# outgoing_connection.net
KiCad netlist of a schematic drawn in Altium Designer
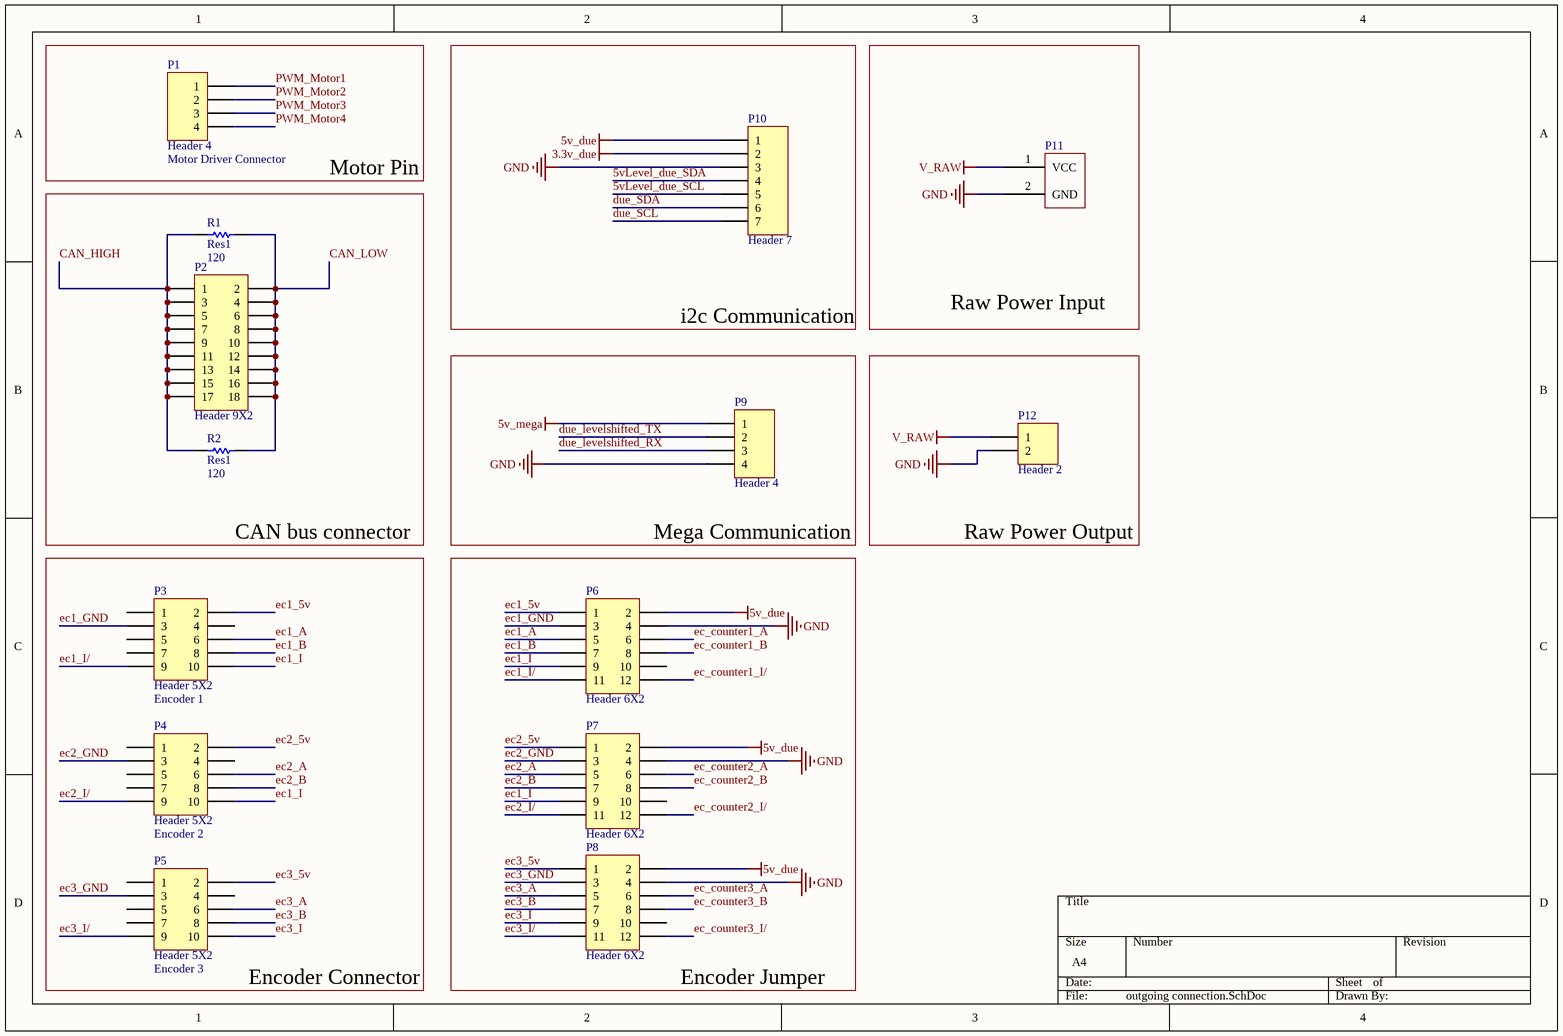
[diagram p0: outgoing connection.SchDoc]

(export (version "E")
  (design (tool "Eeschema 10.0.6"))
  (components
    (comp (ref "P1")
      (value "Header 4")
      (footprint "HDR1X4")
      (description "Header, 4-Pin")
      (fields (field (name "USAGE") "Motor Driver Connector") (field (name "PUBLISHER") "Altium Limited"))
      (libsource (lib "") (part "Header 4_1"))
    )
    (comp (ref "P2")
      (value "Header 9X2")
      (footprint "HDR2X9")
      (description "Header, 9-Pin, Dual row")
      (fields (field (name "PUBLISHER") "Altium Limited"))
      (libsource (lib "Miscellaneous Connectors") (part "Header 9X2"))
    )
    (comp (ref "P3")
      (value "Header 5X2")
      (footprint "HDR2X5")
      (description "Header, 5-Pin, Dual row")
      (fields (field (name "USAGE") "Encoder 1") (field (name "PUBLISHER") "Altium Limited"))
      (libsource (lib "Miscellaneous Connectors") (part "Header 5X2"))
    )
    (comp (ref "P4")
      (value "Header 5X2")
      (footprint "HDR2X5")
      (description "Header, 5-Pin, Dual row")
      (fields (field (name "USAGE") "Encoder 2") (field (name "PUBLISHER") "Altium Limited"))
      (libsource (lib "Miscellaneous Connectors") (part "Header 5X2"))
    )
    (comp (ref "P5")
      (value "Header 5X2")
      (footprint "HDR2X5")
      (description "Header, 5-Pin, Dual row")
      (fields (field (name "USAGE") "Encoder 3") (field (name "PUBLISHER") "Altium Limited"))
      (libsource (lib "Miscellaneous Connectors") (part "Header 5X2"))
    )
    (comp (ref "P6")
      (value "Header 6X2")
      (footprint "HDR2X6")
      (description "Header, 6-Pin, Dual row")
      (fields (field (name "PUBLISHER") "Altium Limited"))
      (libsource (lib "Miscellaneous Connectors") (part "Header 6X2"))
    )
    (comp (ref "P7")
      (value "Header 6X2")
      (footprint "HDR2X6")
      (description "Header, 6-Pin, Dual row")
      (fields (field (name "PUBLISHER") "Altium Limited"))
      (libsource (lib "Miscellaneous Connectors") (part "Header 6X2"))
    )
    (comp (ref "P8")
      (value "Header 6X2")
      (footprint "HDR2X6")
      (description "Header, 6-Pin, Dual row")
      (fields (field (name "PUBLISHER") "Altium Limited"))
      (libsource (lib "Miscellaneous Connectors") (part "Header 6X2"))
    )
    (comp (ref "P9")
      (value "Header 4")
      (footprint "HDR1X4")
      (description "Header, 4-Pin")
      (fields (field (name "PUBLISHER") "Altium Limited"))
      (libsource (lib "Miscellaneous Connectors") (part "Header 4"))
    )
    (comp (ref "P10")
      (value "Header 7")
      (footprint "HDR1X7")
      (description "Header, 7-Pin")
      (fields (field (name "PUBLISHER") "Altium Limited"))
      (libsource (lib "Miscellaneous Connectors") (part "Header 7"))
    )
    (comp (ref "P11")
      (value "big Pin power port")
      (footprint "bigPin_power_port")
      (libsource (lib "bigPin_power_port") (part "big Pin power port"))
    )
    (comp (ref "P12")
      (value "Header 2")
      (footprint "HDR1X2")
      (description "Header, 2-Pin")
      (fields (field (name "PUBLISHER") "Altium Limited"))
      (libsource (lib "Miscellaneous Connectors") (part "Header 2"))
    )
    (comp (ref "R1")
      (value "Res1")
      (footprint "AXIAL-0.3")
      (description "Resistor")
      (fields (field (name "ALTIUM_VALUE") "120") (field (name "PUBLISHER") "Altium Limited"))
      (libsource (lib "Miscellaneous Devices") (part "Res1"))
    )
    (comp (ref "R2")
      (value "Res1")
      (footprint "AXIAL-0.3")
      (description "Resistor")
      (fields (field (name "ALTIUM_VALUE") "120") (field (name "PUBLISHER") "Altium Limited"))
      (libsource (lib "Miscellaneous Devices") (part "Res1"))
    )
  )
  (nets
    (net (code "1") (name "/5vLevel_due_SCL") (class "Default")
      (node (ref "P10") (pin "5") (pinfunction "5_5") (pintype "passive"))
    )
    (net (code "2") (name "/5vLevel_due_SDA") (class "Default")
      (node (ref "P10") (pin "4") (pinfunction "4_4") (pintype "passive"))
    )
    (net (code "3") (name "/CAN_HIGH") (class "Default")
      (node (ref "P2") (pin "1") (pinfunction "1_1") (pintype "passive"))
      (node (ref "P2") (pin "11") (pinfunction "11_11") (pintype "passive"))
      (node (ref "P2") (pin "13") (pinfunction "13_13") (pintype "passive"))
      (node (ref "P2") (pin "15") (pinfunction "15_15") (pintype "passive"))
      (node (ref "P2") (pin "17") (pinfunction "17_17") (pintype "passive"))
      (node (ref "P2") (pin "3") (pinfunction "3_3") (pintype "passive"))
      (node (ref "P2") (pin "5") (pinfunction "5_5") (pintype "passive"))
      (node (ref "P2") (pin "7") (pinfunction "7_7") (pintype "passive"))
      (node (ref "P2") (pin "9") (pinfunction "9_9") (pintype "passive"))
      (node (ref "R1") (pin "1") (pinfunction "1_1") (pintype "passive"))
      (node (ref "R2") (pin "1") (pinfunction "1_1") (pintype "passive"))
    )
    (net (code "4") (name "/CAN_LOW") (class "Default")
      (node (ref "P2") (pin "10") (pinfunction "10_10") (pintype "passive"))
      (node (ref "P2") (pin "12") (pinfunction "12_12") (pintype "passive"))
      (node (ref "P2") (pin "14") (pinfunction "14_14") (pintype "passive"))
      (node (ref "P2") (pin "16") (pinfunction "16_16") (pintype "passive"))
      (node (ref "P2") (pin "18") (pinfunction "18_18") (pintype "passive"))
      (node (ref "P2") (pin "2") (pinfunction "2_2") (pintype "passive"))
      (node (ref "P2") (pin "4") (pinfunction "4_4") (pintype "passive"))
      (node (ref "P2") (pin "6") (pinfunction "6_6") (pintype "passive"))
      (node (ref "P2") (pin "8") (pinfunction "8_8") (pintype "passive"))
      (node (ref "R1") (pin "2") (pinfunction "2_2") (pintype "passive"))
      (node (ref "R2") (pin "2") (pinfunction "2_2") (pintype "passive"))
    )
    (net (code "5") (name "/PWM_Motor1") (class "Default")
      (node (ref "P1") (pin "1") (pinfunction "1_1") (pintype "passive"))
    )
    (net (code "6") (name "/PWM_Motor2") (class "Default")
      (node (ref "P1") (pin "2") (pinfunction "2_2") (pintype "passive"))
    )
    (net (code "7") (name "/PWM_Motor3") (class "Default")
      (node (ref "P1") (pin "3") (pinfunction "3_3") (pintype "passive"))
    )
    (net (code "8") (name "/PWM_Motor4") (class "Default")
      (node (ref "P1") (pin "4") (pinfunction "4_4") (pintype "passive"))
    )
    (net (code "9") (name "/due_SCL") (class "Default")
      (node (ref "P10") (pin "7") (pinfunction "7_7") (pintype "passive"))
    )
    (net (code "10") (name "/due_SDA") (class "Default")
      (node (ref "P10") (pin "6") (pinfunction "6_6") (pintype "passive"))
    )
    (net (code "11") (name "/due_levelshifted_RX") (class "Default")
      (node (ref "P9") (pin "3") (pinfunction "3_3") (pintype "passive"))
    )
    (net (code "12") (name "/due_levelshifted_TX") (class "Default")
      (node (ref "P9") (pin "2") (pinfunction "2_2") (pintype "passive"))
    )
    (net (code "13") (name "/ec1_5v") (class "Default")
      (node (ref "P3") (pin "2") (pinfunction "2_2") (pintype "passive"))
      (node (ref "P6") (pin "1") (pinfunction "1_1") (pintype "passive"))
    )
    (net (code "14") (name "/ec1_A") (class "Default")
      (node (ref "P3") (pin "6") (pinfunction "6_6") (pintype "passive"))
      (node (ref "P6") (pin "5") (pinfunction "5_5") (pintype "passive"))
    )
    (net (code "15") (name "/ec1_B") (class "Default")
      (node (ref "P3") (pin "8") (pinfunction "8_8") (pintype "passive"))
      (node (ref "P6") (pin "7") (pinfunction "7_7") (pintype "passive"))
    )
    (net (code "16") (name "/ec1_GND") (class "Default")
      (node (ref "P3") (pin "3") (pinfunction "3_3") (pintype "passive"))
      (node (ref "P6") (pin "3") (pinfunction "3_3") (pintype "passive"))
    )
    (net (code "17") (name "/ec1_I") (class "Default")
      (node (ref "P3") (pin "10") (pinfunction "10_10") (pintype "passive"))
      (node (ref "P4") (pin "10") (pinfunction "10_10") (pintype "passive"))
      (node (ref "P6") (pin "9") (pinfunction "9_9") (pintype "passive"))
      (node (ref "P7") (pin "9") (pinfunction "9_9") (pintype "passive"))
    )
    (net (code "18") (name "/ec1_I{slash}") (class "Default")
      (node (ref "P3") (pin "9") (pinfunction "9_9") (pintype "passive"))
      (node (ref "P6") (pin "11") (pinfunction "11_11") (pintype "passive"))
    )
    (net (code "19") (name "/ec2_5v") (class "Default")
      (node (ref "P4") (pin "2") (pinfunction "2_2") (pintype "passive"))
      (node (ref "P7") (pin "1") (pinfunction "1_1") (pintype "passive"))
    )
    (net (code "20") (name "/ec2_A") (class "Default")
      (node (ref "P4") (pin "6") (pinfunction "6_6") (pintype "passive"))
      (node (ref "P7") (pin "5") (pinfunction "5_5") (pintype "passive"))
    )
    (net (code "21") (name "/ec2_B") (class "Default")
      (node (ref "P4") (pin "8") (pinfunction "8_8") (pintype "passive"))
      (node (ref "P7") (pin "7") (pinfunction "7_7") (pintype "passive"))
    )
    (net (code "22") (name "/ec2_GND") (class "Default")
      (node (ref "P4") (pin "3") (pinfunction "3_3") (pintype "passive"))
      (node (ref "P7") (pin "3") (pinfunction "3_3") (pintype "passive"))
    )
    (net (code "23") (name "/ec2_I{slash}") (class "Default")
      (node (ref "P4") (pin "9") (pinfunction "9_9") (pintype "passive"))
      (node (ref "P7") (pin "11") (pinfunction "11_11") (pintype "passive"))
    )
    (net (code "24") (name "/ec3_5v") (class "Default")
      (node (ref "P5") (pin "2") (pinfunction "2_2") (pintype "passive"))
      (node (ref "P8") (pin "1") (pinfunction "1_1") (pintype "passive"))
    )
    (net (code "25") (name "/ec3_A") (class "Default")
      (node (ref "P5") (pin "6") (pinfunction "6_6") (pintype "passive"))
      (node (ref "P8") (pin "5") (pinfunction "5_5") (pintype "passive"))
    )
    (net (code "26") (name "/ec3_B") (class "Default")
      (node (ref "P5") (pin "8") (pinfunction "8_8") (pintype "passive"))
      (node (ref "P8") (pin "7") (pinfunction "7_7") (pintype "passive"))
    )
    (net (code "27") (name "/ec3_GND") (class "Default")
      (node (ref "P5") (pin "3") (pinfunction "3_3") (pintype "passive"))
      (node (ref "P8") (pin "3") (pinfunction "3_3") (pintype "passive"))
    )
    (net (code "28") (name "/ec3_I") (class "Default")
      (node (ref "P5") (pin "10") (pinfunction "10_10") (pintype "passive"))
      (node (ref "P8") (pin "9") (pinfunction "9_9") (pintype "passive"))
    )
    (net (code "29") (name "/ec3_I{slash}") (class "Default")
      (node (ref "P5") (pin "9") (pinfunction "9_9") (pintype "passive"))
      (node (ref "P8") (pin "11") (pinfunction "11_11") (pintype "passive"))
    )
    (net (code "30") (name "/ec_counter1_A") (class "Default")
      (node (ref "P6") (pin "6") (pinfunction "6_6") (pintype "passive"))
    )
    (net (code "31") (name "/ec_counter1_B") (class "Default")
      (node (ref "P6") (pin "8") (pinfunction "8_8") (pintype "passive"))
    )
    (net (code "32") (name "/ec_counter1_I{slash}") (class "Default")
      (node (ref "P6") (pin "12") (pinfunction "12_12") (pintype "passive"))
    )
    (net (code "33") (name "/ec_counter2_A") (class "Default")
      (node (ref "P7") (pin "6") (pinfunction "6_6") (pintype "passive"))
    )
    (net (code "34") (name "/ec_counter2_B") (class "Default")
      (node (ref "P7") (pin "8") (pinfunction "8_8") (pintype "passive"))
    )
    (net (code "35") (name "/ec_counter2_I{slash}") (class "Default")
      (node (ref "P7") (pin "12") (pinfunction "12_12") (pintype "passive"))
    )
    (net (code "36") (name "/ec_counter3_A") (class "Default")
      (node (ref "P8") (pin "6") (pinfunction "6_6") (pintype "passive"))
    )
    (net (code "37") (name "/ec_counter3_B") (class "Default")
      (node (ref "P8") (pin "8") (pinfunction "8_8") (pintype "passive"))
    )
    (net (code "38") (name "/ec_counter3_I{slash}") (class "Default")
      (node (ref "P8") (pin "12") (pinfunction "12_12") (pintype "passive"))
    )
    (net (code "39") (name "3.3v_due") (class "Default")
      (node (ref "P10") (pin "2") (pinfunction "2_2") (pintype "passive"))
    )
    (net (code "40") (name "5v_due") (class "Default")
      (node (ref "P10") (pin "1") (pinfunction "1_1") (pintype "passive"))
      (node (ref "P6") (pin "2") (pinfunction "2_2") (pintype "passive"))
      (node (ref "P7") (pin "2") (pinfunction "2_2") (pintype "passive"))
      (node (ref "P8") (pin "2") (pinfunction "2_2") (pintype "passive"))
    )
    (net (code "41") (name "5v_mega") (class "Default")
      (node (ref "P9") (pin "1") (pinfunction "1_1") (pintype "passive"))
    )
    (net (code "42") (name "GND") (class "Default")
      (node (ref "P10") (pin "3") (pinfunction "3_3") (pintype "passive"))
      (node (ref "P11") (pin "2") (pinfunction "GND_2") (pintype "passive"))
      (node (ref "P12") (pin "2") (pinfunction "2_2") (pintype "passive"))
      (node (ref "P6") (pin "4") (pinfunction "4_4") (pintype "passive"))
      (node (ref "P7") (pin "4") (pinfunction "4_4") (pintype "passive"))
      (node (ref "P8") (pin "4") (pinfunction "4_4") (pintype "passive"))
      (node (ref "P9") (pin "4") (pinfunction "4_4") (pintype "passive"))
    )
    (net (code "43") (name "V_RAW") (class "Default")
      (node (ref "P11") (pin "1") (pinfunction "VCC_1") (pintype "passive"))
      (node (ref "P12") (pin "1") (pinfunction "1_1") (pintype "passive"))
    )
    (net (code "44") (name "unconnected-(P3-Pad1)") (class "Default")
      (node (ref "P3") (pin "1") (pinfunction "1_1") (pintype "passive"))
    )
    (net (code "45") (name "unconnected-(P3-Pad4)") (class "Default")
      (node (ref "P3") (pin "4") (pinfunction "4_4") (pintype "passive"))
    )
    (net (code "46") (name "unconnected-(P3-Pad5)") (class "Default")
      (node (ref "P3") (pin "5") (pinfunction "5_5") (pintype "passive"))
    )
    (net (code "47") (name "unconnected-(P3-Pad7)") (class "Default")
      (node (ref "P3") (pin "7") (pinfunction "7_7") (pintype "passive"))
    )
    (net (code "48") (name "unconnected-(P4-Pad1)") (class "Default")
      (node (ref "P4") (pin "1") (pinfunction "1_1") (pintype "passive"))
    )
    (net (code "49") (name "unconnected-(P4-Pad4)") (class "Default")
      (node (ref "P4") (pin "4") (pinfunction "4_4") (pintype "passive"))
    )
    (net (code "50") (name "unconnected-(P4-Pad5)") (class "Default")
      (node (ref "P4") (pin "5") (pinfunction "5_5") (pintype "passive"))
    )
    (net (code "51") (name "unconnected-(P4-Pad7)") (class "Default")
      (node (ref "P4") (pin "7") (pinfunction "7_7") (pintype "passive"))
    )
    (net (code "52") (name "unconnected-(P5-Pad1)") (class "Default")
      (node (ref "P5") (pin "1") (pinfunction "1_1") (pintype "passive"))
    )
    (net (code "53") (name "unconnected-(P5-Pad4)") (class "Default")
      (node (ref "P5") (pin "4") (pinfunction "4_4") (pintype "passive"))
    )
    (net (code "54") (name "unconnected-(P5-Pad5)") (class "Default")
      (node (ref "P5") (pin "5") (pinfunction "5_5") (pintype "passive"))
    )
    (net (code "55") (name "unconnected-(P5-Pad7)") (class "Default")
      (node (ref "P5") (pin "7") (pinfunction "7_7") (pintype "passive"))
    )
    (net (code "56") (name "unconnected-(P6-Pad10)") (class "Default")
      (node (ref "P6") (pin "10") (pinfunction "10_10") (pintype "passive"))
    )
    (net (code "57") (name "unconnected-(P7-Pad10)") (class "Default")
      (node (ref "P7") (pin "10") (pinfunction "10_10") (pintype "passive"))
    )
    (net (code "58") (name "unconnected-(P8-Pad10)") (class "Default")
      (node (ref "P8") (pin "10") (pinfunction "10_10") (pintype "passive"))
    )
  )
)
